# ROV_main_board_sch.net
KiCad netlist of a schematic drawn in Altium Designer
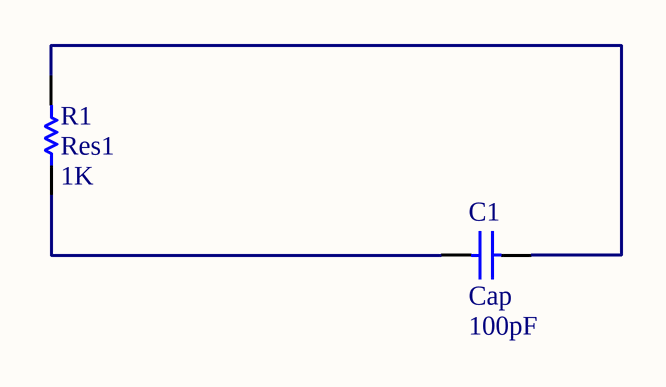
[diagram p0: ROV_main_board_sch.SchDoc]

(export (version "E")
  (design (tool "Eeschema 10.0.6"))
  (components
    (comp (ref "C1")
      (value "Cap")
      (footprint "RAD-0.3")
      (description "Capacitor")
      (fields (field (name "ALTIUM_VALUE") "100pF") (field (name "PUBLISHER") "Altium Limited"))
      (libsource (lib "Miscellaneous Devices") (part "Cap"))
    )
    (comp (ref "R1")
      (value "Res1")
      (footprint "AXIAL-0.3")
      (description "Resistor")
      (fields (field (name "ALTIUM_VALUE") "1K") (field (name "PUBLISHER") "Altium Limited"))
      (libsource (lib "Miscellaneous Devices") (part "Res1"))
    )
  )
  (nets
    (net (code "1") (name "Net-(C1-Pad1)") (class "Default")
      (node (ref "C1") (pin "1") (pinfunction "1_1") (pintype "passive"))
      (node (ref "R1") (pin "1") (pinfunction "1_1") (pintype "passive"))
    )
    (net (code "2") (name "Net-(C1-Pad2)") (class "Default")
      (node (ref "C1") (pin "2") (pinfunction "2_2") (pintype "passive"))
      (node (ref "R1") (pin "2") (pinfunction "2_2") (pintype "passive"))
    )
  )
)
